# Onboard_IO.net
KiCad netlist of a schematic drawn in Altium Designer
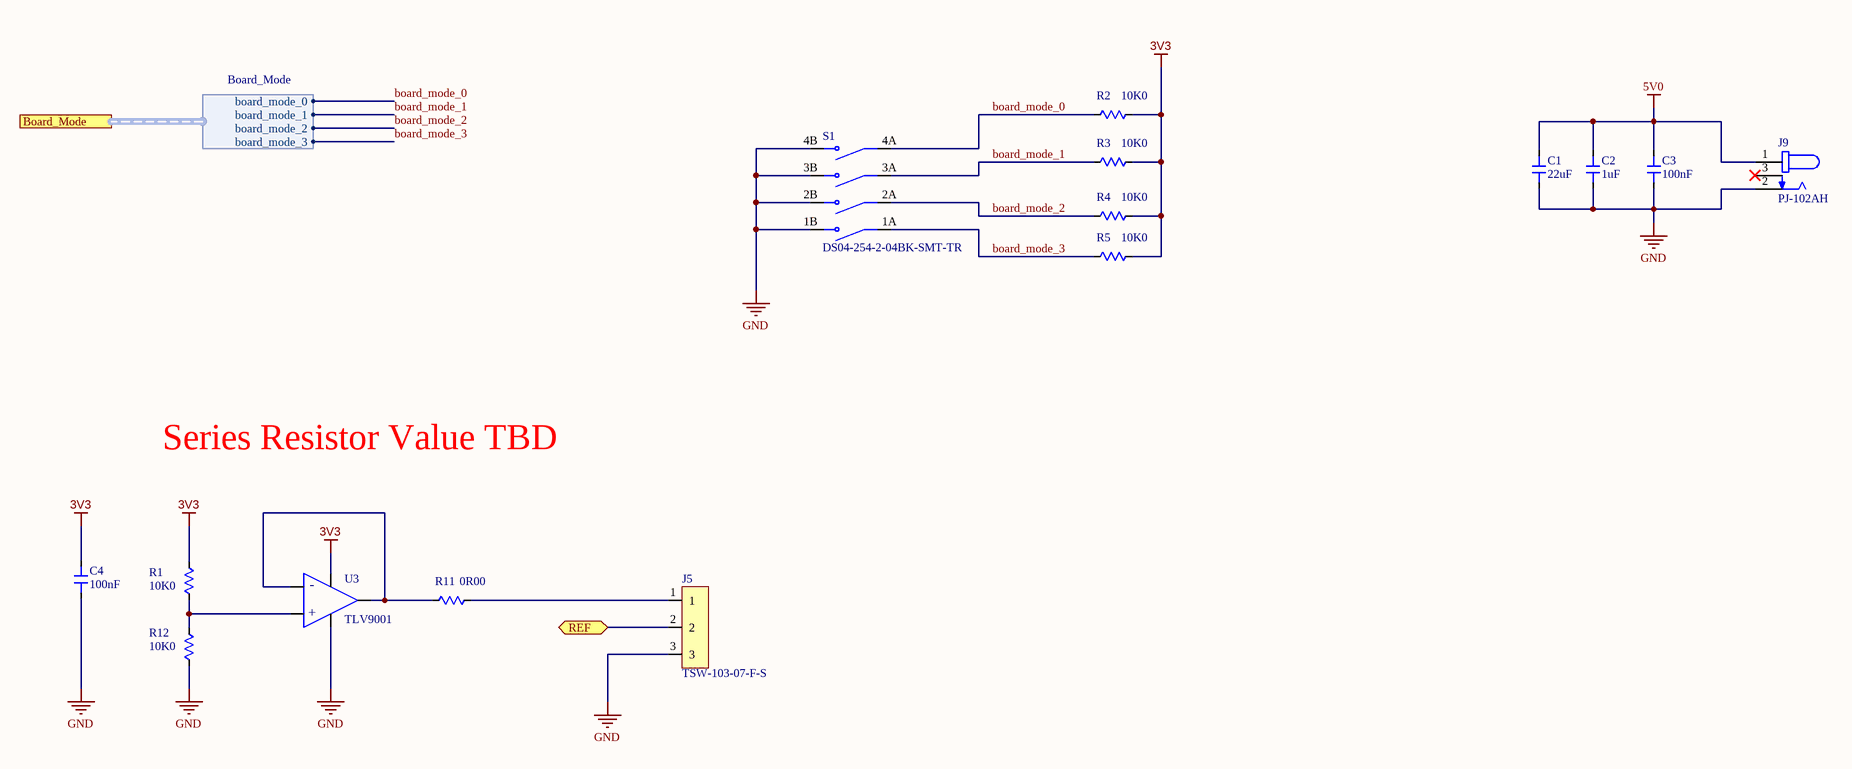
[diagram p0: Onboard_IO.SchDoc]

(export (version "E")
  (design (tool "Eeschema 10.0.6"))
  (components
    (comp (ref "C1")
      (value "22uF")
      (footprint "0805_CAPACITOR")
      (description "Capacitor")
      (libsource (lib "UHDEMG") (part "Capacitor"))
    )
    (comp (ref "C2")
      (value "1uF")
      (footprint "0603_CAPACITOR")
      (description "Capacitor")
      (libsource (lib "UHDEMG") (part "Capacitor"))
    )
    (comp (ref "C3")
      (value "100nF")
      (footprint "0603_CAPACITOR")
      (description "Capacitor")
      (libsource (lib "UHDEMG") (part "Capacitor"))
    )
    (comp (ref "C4")
      (value "100nF")
      (footprint "0603_CAPACITOR")
      (description "Capacitor")
      (libsource (lib "UHDEMG") (part "Capacitor"))
    )
    (comp (ref "J5")
      (value "TSW-103-07-F-S")
      (footprint "SMTC-TSW-103-07-X-S")
      (description "0.025\" SQ Post Header, Through-hole, Vertical, -55 to 125 degC, 2.54 mm Pitch, 3-Pin, Male, RoHS")
      (libsource (lib "UHDEMG") (part "CON_HEADER_1X3"))
    )
    (comp (ref "J9")
      (value "PJ-102AH")
      (footprint "CUI_PJ-102AH")
      (description "Power Barrel Connector Jack 2.00mm ID (0.079\"), 5.50mm OD (0.217\") Through Hole, Right Angle")
      (fields (field (name "MF") "Same Sky"))
      (libsource (lib "UHDEMG") (part "CON_PWR_24V_5A"))
    )
    (comp (ref "R1")
      (value "10K0")
      (footprint "0603_RESISTOR")
      (description "Resistor")
      (libsource (lib "UHDEMG") (part "Resistor"))
    )
    (comp (ref "R2")
      (value "10K0")
      (footprint "0603_RESISTOR")
      (description "Resistor")
      (libsource (lib "UHDEMG") (part "Resistor"))
    )
    (comp (ref "R3")
      (value "10K0")
      (footprint "0603_RESISTOR")
      (description "Resistor")
      (libsource (lib "UHDEMG") (part "Resistor"))
    )
    (comp (ref "R4")
      (value "10K0")
      (footprint "0603_RESISTOR")
      (description "Resistor")
      (libsource (lib "UHDEMG") (part "Resistor"))
    )
    (comp (ref "R5")
      (value "10K0")
      (footprint "0603_RESISTOR")
      (description "Resistor")
      (libsource (lib "UHDEMG") (part "Resistor"))
    )
    (comp (ref "R11")
      (value "0R00")
      (footprint "0603_RESISTOR")
      (description "Resistor")
      (libsource (lib "UHDEMG") (part "Resistor"))
    )
    (comp (ref "R12")
      (value "10K0")
      (footprint "0603_RESISTOR")
      (description "Resistor")
      (libsource (lib "UHDEMG") (part "Resistor"))
    )
    (comp (ref "S1")
      (value "DS04-254-2-04BK-SMT-TR")
      (footprint "SW_DS04-254-2-04BK-SMT-TR")
      (description "Dip Switch SPST 4 Position Surface Mount Slide (Standard) Actuator 25mA 24VDC")
      (fields (field (name "MF") "Same Sky"))
      (libsource (lib "UHDEMG") (part "SW_DIP_4_SMT"))
    )
    (comp (ref "U3")
      (value "TLV9001")
      (footprint "SOT-353")
      (description "CMOS Amplifier 1 Circuit Rail-to-Rail SC-70-5\r\n1.8V - 5.5V")
      (libsource (lib "UHDEMG") (part "IC_OP_AMP_1CH"))
    )
  )
  (nets
    (net (code "2") (name "/REF") (class "Default")
      (node (ref "J5") (pin "2") (pinfunction "2_2") (pintype "passive"))
    )
    (net (code "3") (name "/board_mode_0") (class "Default")
      (node (ref "R2") (pin "1") (pinfunction "1_1") (pintype "passive"))
      (node (ref "S1") (pin "4A") (pinfunction "COM4_4A") (pintype "passive"))
    )
    (net (code "4") (name "/board_mode_1") (class "Default")
      (node (ref "R3") (pin "1") (pinfunction "1_1") (pintype "passive"))
      (node (ref "S1") (pin "3A") (pinfunction "COM3_3A") (pintype "passive"))
    )
    (net (code "5") (name "/board_mode_2") (class "Default")
      (node (ref "R4") (pin "1") (pinfunction "1_1") (pintype "passive"))
      (node (ref "S1") (pin "2A") (pinfunction "COM2_2A") (pintype "passive"))
    )
    (net (code "6") (name "/board_mode_3") (class "Default")
      (node (ref "R5") (pin "1") (pinfunction "1_1") (pintype "passive"))
      (node (ref "S1") (pin "1A") (pinfunction "COM1_1A") (pintype "passive"))
    )
    (net (code "8") (name "3V3") (class "Default")
      (node (ref "C4") (pin "2") (pinfunction "2_2") (pintype "passive"))
      (node (ref "R1") (pin "1") (pinfunction "1_1") (pintype "passive"))
      (node (ref "R2") (pin "2") (pinfunction "2_2") (pintype "passive"))
      (node (ref "R3") (pin "2") (pinfunction "2_2") (pintype "passive"))
      (node (ref "R4") (pin "2") (pinfunction "2_2") (pintype "passive"))
      (node (ref "R5") (pin "2") (pinfunction "2_2") (pintype "passive"))
      (node (ref "U3") (pin "5") (pinfunction "V+_5") (pintype "passive"))
    )
    (net (code "9") (name "5V0") (class "Default")
      (node (ref "C1") (pin "2") (pinfunction "2_2") (pintype "passive"))
      (node (ref "C2") (pin "2") (pinfunction "2_2") (pintype "passive"))
      (node (ref "C3") (pin "2") (pinfunction "2_2") (pintype "passive"))
      (node (ref "J9") (pin "1") (pinfunction "1_1") (pintype "passive"))
    )
    (net (code "10") (name "GND") (class "Default")
      (node (ref "C1") (pin "1") (pinfunction "1_1") (pintype "passive"))
      (node (ref "C2") (pin "1") (pinfunction "1_1") (pintype "passive"))
      (node (ref "C3") (pin "1") (pinfunction "1_1") (pintype "passive"))
      (node (ref "C4") (pin "1") (pinfunction "1_1") (pintype "passive"))
      (node (ref "J5") (pin "3") (pinfunction "3_3") (pintype "passive"))
      (node (ref "J9") (pin "2") (pinfunction "2_2") (pintype "passive"))
      (node (ref "R12") (pin "2") (pinfunction "2_2") (pintype "passive"))
      (node (ref "S1") (pin "1B") (pinfunction "NO1_1B") (pintype "passive"))
      (node (ref "S1") (pin "2B") (pinfunction "NO2_2B") (pintype "passive"))
      (node (ref "S1") (pin "3B") (pinfunction "NO3_3B") (pintype "passive"))
      (node (ref "S1") (pin "4B") (pinfunction "NO4_4B") (pintype "passive"))
      (node (ref "U3") (pin "2") (pinfunction "V-_2") (pintype "passive"))
    )
    (net (code "11") (name "Net-(J5-Pad1)") (class "Default")
      (node (ref "J5") (pin "1") (pinfunction "1_1") (pintype "passive"))
      (node (ref "R11") (pin "2") (pinfunction "2_2") (pintype "passive"))
    )
    (net (code "12") (name "Net-(U3-IN+)") (class "Default")
      (node (ref "R1") (pin "2") (pinfunction "2_2") (pintype "passive"))
      (node (ref "R12") (pin "1") (pinfunction "1_1") (pintype "passive"))
      (node (ref "U3") (pin "3") (pinfunction "IN+_3") (pintype "passive"))
    )
    (net (code "13") (name "Net-(U3-IN-)") (class "Default")
      (node (ref "R11") (pin "1") (pinfunction "1_1") (pintype "passive"))
      (node (ref "U3") (pin "1") (pinfunction "Out_1") (pintype "passive"))
      (node (ref "U3") (pin "4") (pinfunction "IN-_4") (pintype "passive"))
    )
    (net (code "14") (name "unconnected-(J9-Pad3)") (class "Default")
      (node (ref "J9") (pin "3") (pinfunction "3_3") (pintype "passive+no_connect"))
    )
  )
)
